# Zio_Rotary_Encoder_Sensor.net
KiCad netlist of a schematic drawn in EAGLE
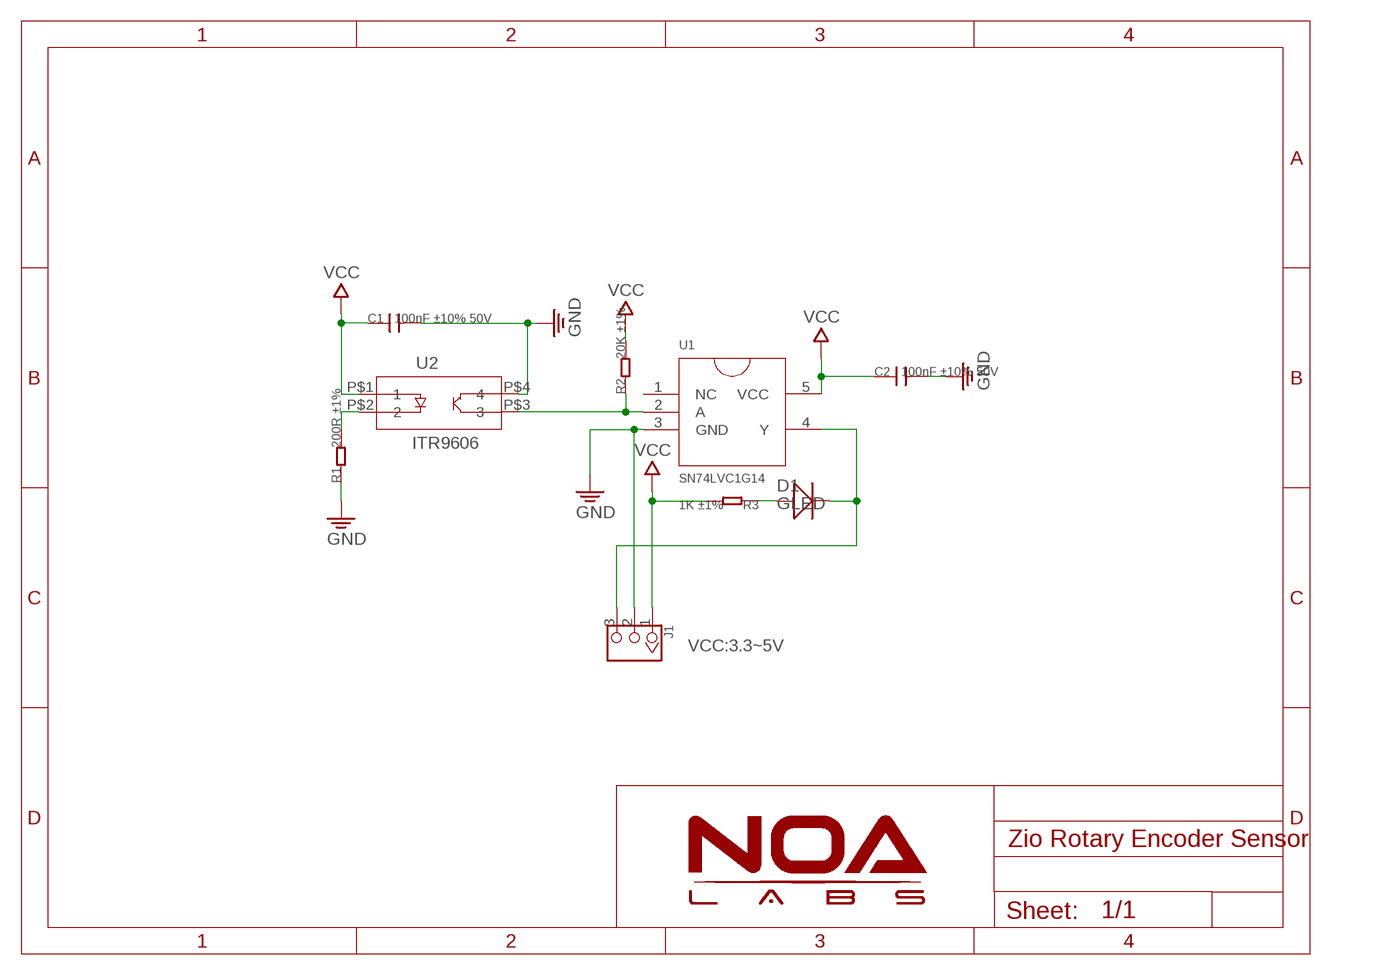
[diagram p0: schematic, sheet 1]

(export (version "E")
  (design (tool "Eeschema 10.0.6"))
  (components
    (comp (ref "C1")
      (value "100nF ±10% 50V")
      (footprint "eagle-import:0603")
      (libsource (lib "eagle-import") (part "C-0603"))
    )
    (comp (ref "C2")
      (value "100nF ±10% 50V")
      (footprint "eagle-import:0603")
      (libsource (lib "eagle-import") (part "C-0603"))
    )
    (comp (ref "D1")
      (value "GLED")
      (footprint "eagle-import:SOD523")
      (libsource (lib "eagle-import") (part "D-0603"))
    )
    (comp (ref "J1")
      (value "HEADER-3P-2.54")
      (footprint "eagle-import:3P-2.54")
      (libsource (lib "eagle-import") (part "HEADER-3P-2.54"))
    )
    (comp (ref "R1")
      (value "200R ±1%")
      (footprint "eagle-import:0603")
      (libsource (lib "eagle-import") (part "R-0603"))
    )
    (comp (ref "R2")
      (value "20K ±1%")
      (footprint "eagle-import:0603")
      (libsource (lib "eagle-import") (part "R-0603"))
    )
    (comp (ref "R3")
      (value "1K ±1%")
      (footprint "eagle-import:0603")
      (libsource (lib "eagle-import") (part "R-0603"))
    )
    (comp (ref "U1")
      (value "SN74LVC1G14")
      (footprint "eagle-import:SOT23-5")
      (libsource (lib "eagle-import") (part "SN74LVC1G14"))
    )
    (comp (ref "U2")
      (value "ITR9606")
      (footprint "eagle-import:ITR9606")
      (libsource (lib "eagle-import") (part "ITR9606"))
    )
  )
  (nets
    (net (code "1") (name "GND") (class "Default")
      (node (ref "C1") (pin "2") (pinfunction "2_2") (pintype "passive"))
      (node (ref "C2") (pin "2") (pinfunction "2_2") (pintype "passive"))
      (node (ref "J1") (pin "2") (pinfunction "P$2_2") (pintype "bidirectional"))
      (node (ref "R1") (pin "1") (pinfunction "1_1") (pintype "passive"))
      (node (ref "U1") (pin "3") (pinfunction "GND_3") (pintype "bidirectional"))
      (node (ref "U2") (pin "P$4") (pinfunction "4_P$4") (pintype "bidirectional"))
    )
    (net (code "2") (name "Net-(D1-Pad+)") (class "Default")
      (node (ref "D1") (pin "+") (pinfunction "+_+") (pintype "passive"))
      (node (ref "R3") (pin "1") (pinfunction "1_1") (pintype "passive"))
    )
    (net (code "3") (name "Net-(J1-P$3)") (class "Default")
      (node (ref "D1") (pin "-") (pinfunction "-_-") (pintype "passive"))
      (node (ref "J1") (pin "3") (pinfunction "P$3_3") (pintype "bidirectional"))
      (node (ref "U1") (pin "4") (pinfunction "Y_4") (pintype "bidirectional"))
    )
    (net (code "4") (name "Net-(U1-A)") (class "Default")
      (node (ref "R2") (pin "1") (pinfunction "1_1") (pintype "passive"))
      (node (ref "U1") (pin "2") (pinfunction "A_2") (pintype "bidirectional"))
      (node (ref "U2") (pin "P$3") (pinfunction "3_P$3") (pintype "bidirectional"))
    )
    (net (code "5") (name "Net-(U2-2)") (class "Default")
      (node (ref "R1") (pin "2") (pinfunction "2_2") (pintype "passive"))
      (node (ref "U2") (pin "P$2") (pinfunction "2_P$2") (pintype "bidirectional"))
    )
    (net (code "6") (name "VCC") (class "Default")
      (node (ref "C1") (pin "1") (pinfunction "1_1") (pintype "passive"))
      (node (ref "C2") (pin "1") (pinfunction "1_1") (pintype "passive"))
      (node (ref "J1") (pin "1") (pinfunction "P$1_1") (pintype "bidirectional"))
      (node (ref "R2") (pin "2") (pinfunction "2_2") (pintype "passive"))
      (node (ref "R3") (pin "2") (pinfunction "2_2") (pintype "passive"))
      (node (ref "U1") (pin "5") (pinfunction "VCC_5") (pintype "bidirectional"))
      (node (ref "U2") (pin "P$1") (pinfunction "1_P$1") (pintype "bidirectional"))
    )
    (net (code "7") (name "unconnected-(U1-NC-Pad1)") (class "Default")
      (node (ref "U1") (pin "1") (pinfunction "NC_1") (pintype "bidirectional"))
    )
  )
)
